# sensor02.net
KiCad netlist of a schematic drawn in EAGLE
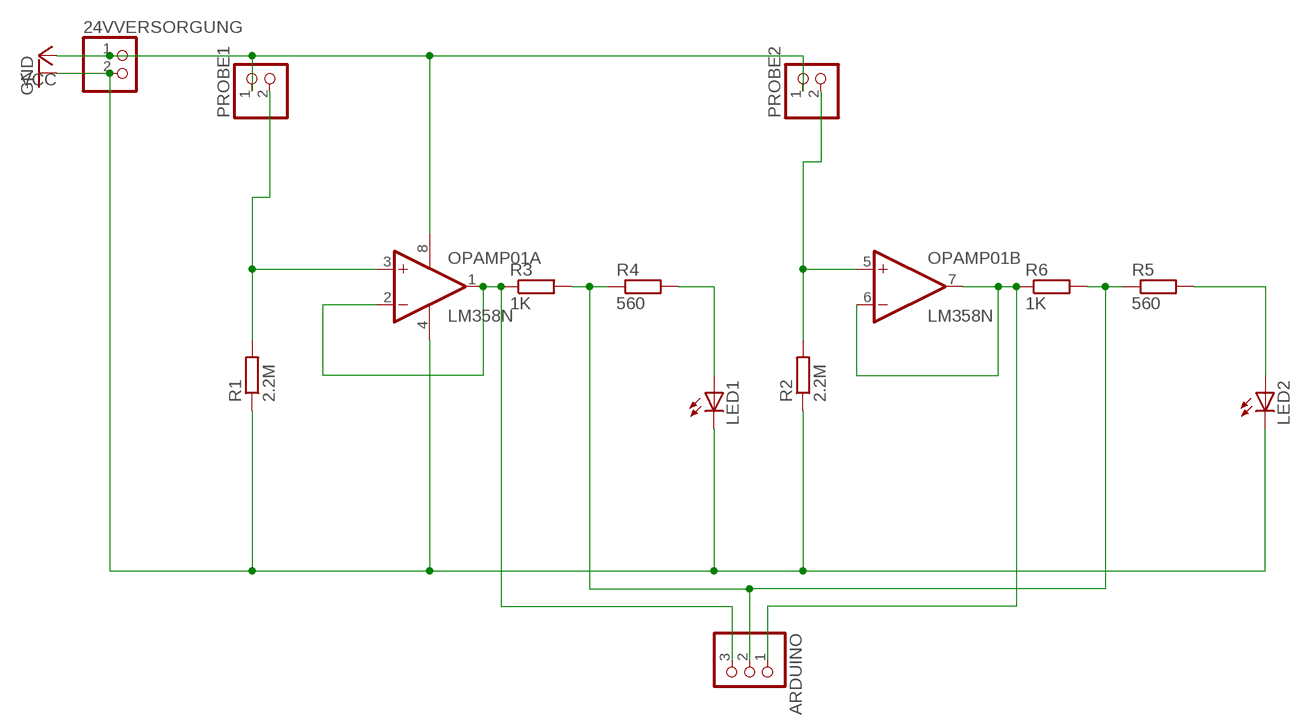
[diagram p0: schematic, sheet 1]

(export (version "E")
  (design (tool "Eeschema 10.0.6"))
  (components
    (comp (ref "24VVERSORGUNG")
      (value "PINHD-1X2")
      (footprint "eagle-import:1X02")
      (libsource (lib "eagle-import") (part "PINHD-1X2"))
    )
    (comp (ref "ARDUINO")
      (value "PINHD-1X3")
      (footprint "eagle-import:1X03")
      (libsource (lib "eagle-import") (part "PINHD-1X3"))
    )
    (comp (ref "LED1")
      (value "LED5MM")
      (footprint "eagle-import:LED5MM")
      (libsource (lib "eagle-import") (part "LED5MM"))
    )
    (comp (ref "LED2")
      (value "LED5MM")
      (footprint "eagle-import:LED5MM")
      (libsource (lib "eagle-import") (part "LED5MM"))
    )
    (comp (ref "OPAMP01")
      (value "LM358N")
      (footprint "eagle-import:DIL08")
      (libsource (lib "eagle-import") (part "LM358N"))
    )
    (comp (ref "PROBE1")
      (value "PINHD-1X2")
      (footprint "eagle-import:1X02")
      (libsource (lib "eagle-import") (part "PINHD-1X2"))
    )
    (comp (ref "PROBE2")
      (value "PINHD-1X2")
      (footprint "eagle-import:1X02")
      (libsource (lib "eagle-import") (part "PINHD-1X2"))
    )
    (comp (ref "R1")
      (value "2.2M")
      (footprint "eagle-import:0207_7")
      (libsource (lib "eagle-import") (part "R-EU_0207/7"))
    )
    (comp (ref "R2")
      (value "2.2M")
      (footprint "eagle-import:0207_7")
      (libsource (lib "eagle-import") (part "R-EU_0207/7"))
    )
    (comp (ref "R3")
      (value "1K")
      (footprint "eagle-import:0207_7")
      (libsource (lib "eagle-import") (part "R-EU_0207/7"))
    )
    (comp (ref "R4")
      (value "560")
      (footprint "eagle-import:0207_7")
      (libsource (lib "eagle-import") (part "R-EU_0207/7"))
    )
    (comp (ref "R5")
      (value "560")
      (footprint "eagle-import:0207_7")
      (libsource (lib "eagle-import") (part "R-EU_0207/7"))
    )
    (comp (ref "R6")
      (value "1K")
      (footprint "eagle-import:0207_7")
      (libsource (lib "eagle-import") (part "R-EU_0207/7"))
    )
  )
  (nets
    (net (code "1") (name "GND") (class "Default")
      (node (ref "24VVERSORGUNG") (pin "2") (pinfunction "2_2") (pintype "passive"))
      (node (ref "LED1") (pin "K") (pinfunction "C_K") (pintype "passive"))
      (node (ref "LED2") (pin "K") (pinfunction "C_K") (pintype "passive"))
      (node (ref "OPAMP01") (pin "4") (pinfunction "V-_4") (pintype "power_in"))
      (node (ref "R1") (pin "1") (pinfunction "1_1") (pintype "passive"))
      (node (ref "R2") (pin "1") (pinfunction "1_1") (pintype "passive"))
    )
    (net (code "2") (name "Net-(ARDUINO-Pad2)") (class "Default")
      (node (ref "ARDUINO") (pin "2") (pinfunction "2_2") (pintype "passive"))
      (node (ref "R3") (pin "2") (pinfunction "2_2") (pintype "passive"))
      (node (ref "R4") (pin "1") (pinfunction "1_1") (pintype "passive"))
      (node (ref "R5") (pin "1") (pinfunction "1_1") (pintype "passive"))
      (node (ref "R6") (pin "2") (pinfunction "2_2") (pintype "passive"))
    )
    (net (code "3") (name "Net-(LED1-PadA)") (class "Default")
      (node (ref "LED1") (pin "A") (pinfunction "A_A") (pintype "passive"))
      (node (ref "R4") (pin "2") (pinfunction "2_2") (pintype "passive"))
    )
    (net (code "4") (name "Net-(LED2-PadA)") (class "Default")
      (node (ref "LED2") (pin "A") (pinfunction "A_A") (pintype "passive"))
      (node (ref "R5") (pin "2") (pinfunction "2_2") (pintype "passive"))
    )
    (net (code "5") (name "Net-(OPAMP01A-+IN)") (class "Default")
      (node (ref "OPAMP01") (pin "3") (pinfunction "+IN_3") (pintype "input"))
      (node (ref "PROBE1") (pin "2") (pinfunction "2_2") (pintype "passive"))
      (node (ref "R1") (pin "2") (pinfunction "2_2") (pintype "passive"))
    )
    (net (code "6") (name "Net-(OPAMP01A--IN)") (class "Default")
      (node (ref "ARDUINO") (pin "3") (pinfunction "3_3") (pintype "passive"))
      (node (ref "OPAMP01") (pin "1") (pinfunction "OUT_1") (pintype "output"))
      (node (ref "OPAMP01") (pin "2") (pinfunction "-IN_2") (pintype "input"))
      (node (ref "R3") (pin "1") (pinfunction "1_1") (pintype "passive"))
    )
    (net (code "7") (name "Net-(OPAMP01B-+IN)") (class "Default")
      (node (ref "OPAMP01") (pin "5") (pinfunction "+IN_5") (pintype "input"))
      (node (ref "PROBE2") (pin "2") (pinfunction "2_2") (pintype "passive"))
      (node (ref "R2") (pin "2") (pinfunction "2_2") (pintype "passive"))
    )
    (net (code "8") (name "Net-(OPAMP01B--IN)") (class "Default")
      (node (ref "ARDUINO") (pin "1") (pinfunction "1_1") (pintype "passive"))
      (node (ref "OPAMP01") (pin "6") (pinfunction "-IN_6") (pintype "input"))
      (node (ref "OPAMP01") (pin "7") (pinfunction "OUT_7") (pintype "output"))
      (node (ref "R6") (pin "1") (pinfunction "1_1") (pintype "passive"))
    )
    (net (code "9") (name "VCC") (class "Default")
      (node (ref "24VVERSORGUNG") (pin "1") (pinfunction "1_1") (pintype "passive"))
      (node (ref "OPAMP01") (pin "8") (pinfunction "V+_8") (pintype "power_in"))
      (node (ref "PROBE1") (pin "1") (pinfunction "1_1") (pintype "passive"))
      (node (ref "PROBE2") (pin "1") (pinfunction "1_1") (pintype "passive"))
    )
  )
)
